# pcf8574.net
KiCad netlist of a schematic drawn in EAGLE
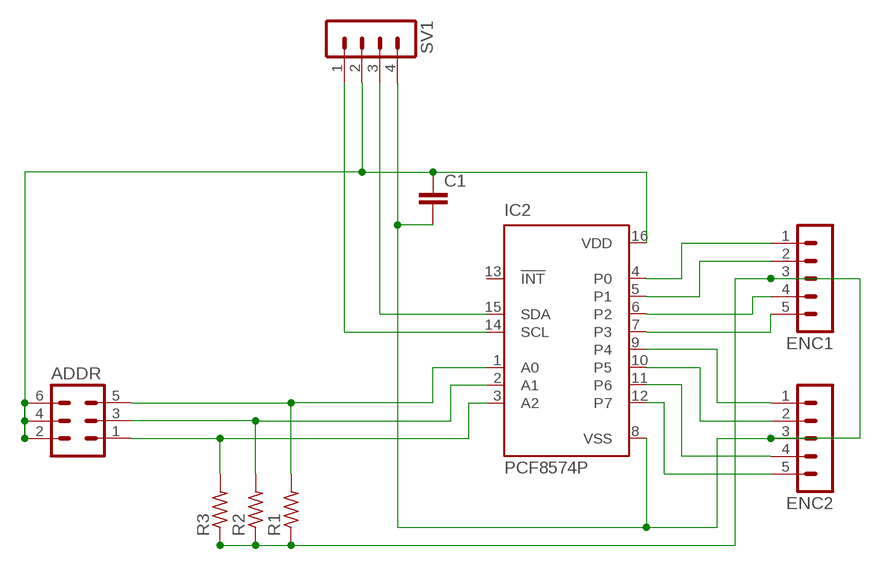
[diagram p0: schematic, sheet 1]

(export (version "E")
  (design (tool "Eeschema 10.0.6"))
  (components
    (comp (ref "ADDR")
      (value "MA03-2")
      (footprint "eagle-import:MA03-2")
      (libsource (lib "eagle-import") (part "MA03-2"))
    )
    (comp (ref "C1")
      (value "C5/2.5")
      (footprint "eagle-import:C5B2.5")
      (libsource (lib "eagle-import") (part "C5/2.5"))
    )
    (comp (ref "ENC1")
      (value "MA05-1")
      (footprint "eagle-import:MA05-1")
      (libsource (lib "eagle-import") (part "MA05-1"))
    )
    (comp (ref "ENC2")
      (value "MA05-1")
      (footprint "eagle-import:MA05-1")
      (libsource (lib "eagle-import") (part "MA05-1"))
    )
    (comp (ref "IC2")
      (value "PCF8574P")
      (footprint "eagle-import:DIL16")
      (fields (field (name "MPN") "PCF8574PN"))
      (libsource (lib "eagle-import") (part "PCF8574P"))
    )
    (comp (ref "R1")
      (value "R-US_0204/7")
      (footprint "eagle-import:0204_7")
      (libsource (lib "eagle-import") (part "R-US_0204/7"))
    )
    (comp (ref "R2")
      (value "R-US_0204/7")
      (footprint "eagle-import:0204_7")
      (libsource (lib "eagle-import") (part "R-US_0204/7"))
    )
    (comp (ref "R3")
      (value "R-US_0204/7")
      (footprint "eagle-import:0204_7")
      (libsource (lib "eagle-import") (part "R-US_0204/7"))
    )
    (comp (ref "SV1")
      (value "MA04-1")
      (footprint "eagle-import:MA04-1")
      (libsource (lib "eagle-import") (part "MA04-1"))
    )
  )
  (nets
    (net (code "1") (name "Net-(IC2-A0)") (class "Default")
      (node (ref "ADDR") (pin "5") (pinfunction "5_5") (pintype "passive"))
      (node (ref "IC2") (pin "1") (pinfunction "A0_1") (pintype "input"))
      (node (ref "R1") (pin "2") (pinfunction "2_2") (pintype "passive"))
    )
    (net (code "2") (name "Net-(IC2-A1)") (class "Default")
      (node (ref "ADDR") (pin "3") (pinfunction "3_3") (pintype "passive"))
      (node (ref "IC2") (pin "2") (pinfunction "A1_2") (pintype "input"))
      (node (ref "R2") (pin "2") (pinfunction "2_2") (pintype "passive"))
    )
    (net (code "3") (name "Net-(IC2-A2)") (class "Default")
      (node (ref "ADDR") (pin "1") (pinfunction "1_1") (pintype "passive"))
      (node (ref "IC2") (pin "3") (pinfunction "A2_3") (pintype "input"))
      (node (ref "R3") (pin "2") (pinfunction "2_2") (pintype "passive"))
    )
    (net (code "4") (name "Net-(IC2-P0)") (class "Default")
      (node (ref "ENC1") (pin "1") (pinfunction "1_1") (pintype "passive"))
      (node (ref "IC2") (pin "4") (pinfunction "P0_4") (pintype "bidirectional"))
    )
    (net (code "5") (name "Net-(IC2-P1)") (class "Default")
      (node (ref "ENC1") (pin "2") (pinfunction "2_2") (pintype "passive"))
      (node (ref "IC2") (pin "5") (pinfunction "P1_5") (pintype "bidirectional"))
    )
    (net (code "6") (name "Net-(IC2-P2)") (class "Default")
      (node (ref "ENC1") (pin "4") (pinfunction "4_4") (pintype "passive"))
      (node (ref "IC2") (pin "6") (pinfunction "P2_6") (pintype "bidirectional"))
    )
    (net (code "7") (name "Net-(IC2-P3)") (class "Default")
      (node (ref "ENC1") (pin "5") (pinfunction "5_5") (pintype "passive"))
      (node (ref "IC2") (pin "7") (pinfunction "P3_7") (pintype "bidirectional"))
    )
    (net (code "8") (name "Net-(IC2-P4)") (class "Default")
      (node (ref "ENC2") (pin "1") (pinfunction "1_1") (pintype "passive"))
      (node (ref "IC2") (pin "9") (pinfunction "P4_9") (pintype "bidirectional"))
    )
    (net (code "9") (name "Net-(IC2-P5)") (class "Default")
      (node (ref "ENC2") (pin "2") (pinfunction "2_2") (pintype "passive"))
      (node (ref "IC2") (pin "10") (pinfunction "P5_10") (pintype "bidirectional"))
    )
    (net (code "10") (name "Net-(IC2-P6)") (class "Default")
      (node (ref "ENC2") (pin "4") (pinfunction "4_4") (pintype "passive"))
      (node (ref "IC2") (pin "11") (pinfunction "P6_11") (pintype "bidirectional"))
    )
    (net (code "11") (name "Net-(IC2-P7)") (class "Default")
      (node (ref "ENC2") (pin "5") (pinfunction "5_5") (pintype "passive"))
      (node (ref "IC2") (pin "12") (pinfunction "P7_12") (pintype "bidirectional"))
    )
    (net (code "12") (name "Net-(IC2-SCL)") (class "Default")
      (node (ref "IC2") (pin "14") (pinfunction "SCL_14") (pintype "input"))
      (node (ref "SV1") (pin "1") (pinfunction "1_1") (pintype "passive"))
    )
    (net (code "13") (name "Net-(IC2-SDA)") (class "Default")
      (node (ref "IC2") (pin "15") (pinfunction "SDA_15") (pintype "bidirectional"))
      (node (ref "SV1") (pin "3") (pinfunction "3_3") (pintype "passive"))
    )
    (net (code "14") (name "Net-(IC2-VDD)") (class "Default")
      (node (ref "ADDR") (pin "2") (pinfunction "2_2") (pintype "passive"))
      (node (ref "ADDR") (pin "4") (pinfunction "4_4") (pintype "passive"))
      (node (ref "ADDR") (pin "6") (pinfunction "6_6") (pintype "passive"))
      (node (ref "C1") (pin "1") (pinfunction "1_1") (pintype "passive"))
      (node (ref "IC2") (pin "16") (pinfunction "VDD_16") (pintype "power_in"))
      (node (ref "SV1") (pin "2") (pinfunction "2_2") (pintype "passive"))
    )
    (net (code "15") (name "Net-(IC2-VSS)") (class "Default")
      (node (ref "C1") (pin "2") (pinfunction "2_2") (pintype "passive"))
      (node (ref "ENC1") (pin "3") (pinfunction "3_3") (pintype "passive"))
      (node (ref "ENC2") (pin "3") (pinfunction "3_3") (pintype "passive"))
      (node (ref "IC2") (pin "8") (pinfunction "VSS_8") (pintype "power_in"))
      (node (ref "R1") (pin "1") (pinfunction "1_1") (pintype "passive"))
      (node (ref "R2") (pin "1") (pinfunction "1_1") (pintype "passive"))
      (node (ref "R3") (pin "1") (pinfunction "1_1") (pintype "passive"))
      (node (ref "SV1") (pin "4") (pinfunction "4_4") (pintype "passive"))
    )
    (net (code "16") (name "unconnected-(IC2-~{INT}-Pad13)") (class "Default")
      (node (ref "IC2") (pin "13") (pinfunction "~{INT}_13") (pintype "output"))
    )
  )
)
